# uArm_back_print.net
KiCad netlist of a schematic drawn in EAGLE
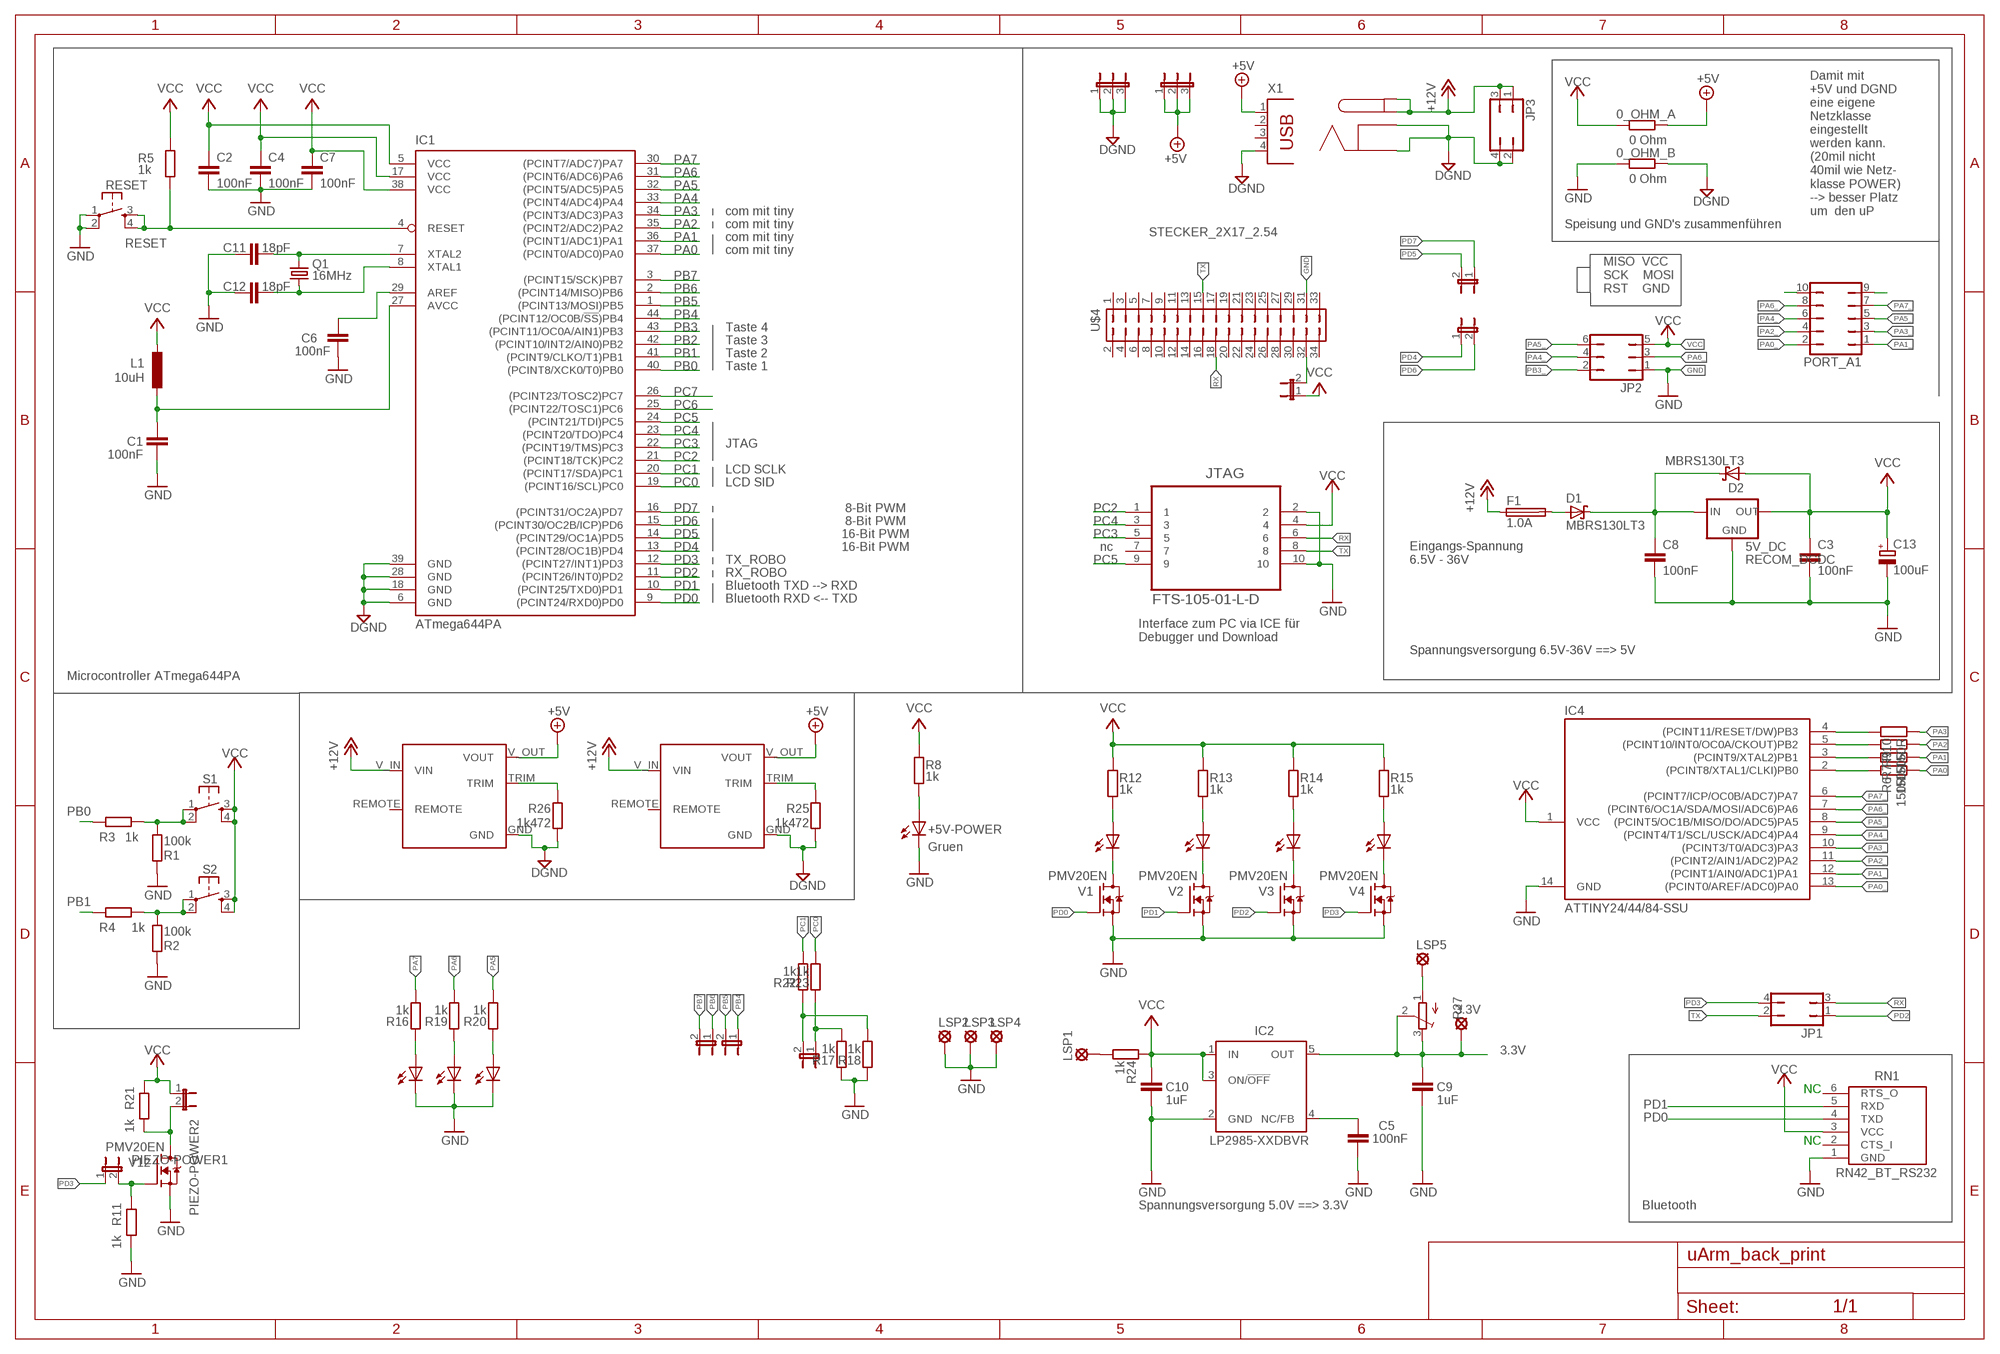
[diagram p0: schematic, sheet 1]

(export (version "E")
  (design (tool "Eeschema 10.0.6"))
  (components
    (comp (ref "+5V-POWER")
      (value "Gruen")
      (footprint "eagle-import:CHIPLED_1206")
      (libsource (lib "eagle-import") (part "LEDCHIPLED_1206"))
    )
    (comp (ref "0_OHM_A")
      (value "0 Ohm")
      (footprint "eagle-import:R0805")
      (libsource (lib "eagle-import") (part "R-EU_R0805"))
    )
    (comp (ref "0_OHM_B")
      (value "0 Ohm")
      (footprint "eagle-import:R0805")
      (libsource (lib "eagle-import") (part "R-EU_R0805"))
    )
    (comp (ref "3.3V")
      (value "3.3V")
      (footprint "eagle-import:LSP11")
      (libsource (lib "eagle-import") (part "LSP11"))
    )
    (comp (ref "5V_DC")
      (value "RECOM_DCDC")
      (footprint "eagle-import:RECOM_DCDC")
      (libsource (lib "eagle-import") (part "RECOM_DCDC"))
    )
    (comp (ref "C1")
      (value "100nF")
      (footprint "eagle-import:C0805")
      (libsource (lib "eagle-import") (part "C-EUC0805"))
    )
    (comp (ref "C2")
      (value "100nF")
      (footprint "eagle-import:C0805")
      (libsource (lib "eagle-import") (part "C-EUC0805"))
    )
    (comp (ref "C3")
      (value "100nF")
      (footprint "eagle-import:C0805")
      (libsource (lib "eagle-import") (part "C-EUC0805"))
    )
    (comp (ref "C4")
      (value "100nF")
      (footprint "eagle-import:C0805")
      (libsource (lib "eagle-import") (part "C-EUC0805"))
    )
    (comp (ref "C5")
      (value "100nF")
      (footprint "eagle-import:C0805")
      (libsource (lib "eagle-import") (part "C-EUC0805"))
    )
    (comp (ref "C6")
      (value "100nF")
      (footprint "eagle-import:C0805")
      (libsource (lib "eagle-import") (part "C-EUC0805"))
    )
    (comp (ref "C7")
      (value "100nF")
      (footprint "eagle-import:C0805")
      (libsource (lib "eagle-import") (part "C-EUC0805"))
    )
    (comp (ref "C8")
      (value "100nF")
      (footprint "eagle-import:C0805")
      (libsource (lib "eagle-import") (part "C-EUC0805"))
    )
    (comp (ref "C9")
      (value "1uF")
      (footprint "eagle-import:C0805")
      (libsource (lib "eagle-import") (part "C-EUC0805"))
    )
    (comp (ref "C10")
      (value "1uF")
      (footprint "eagle-import:C0805")
      (libsource (lib "eagle-import") (part "C-EUC0805"))
    )
    (comp (ref "C11")
      (value "18pF")
      (footprint "eagle-import:C0805")
      (libsource (lib "eagle-import") (part "C-EUC0805"))
    )
    (comp (ref "C12")
      (value "18pF")
      (footprint "eagle-import:C0805")
      (libsource (lib "eagle-import") (part "C-EUC0805"))
    )
    (comp (ref "C13")
      (value "100uF")
      (footprint "eagle-import:UD-6,3X5,8_NICHICON")
      (libsource (lib "eagle-import") (part "CPOL-EUUD-6,3X8,8"))
    )
    (comp (ref "D1")
      (value "MBRS130LT3")
      (footprint "eagle-import:SMB")
      (libsource (lib "eagle-import") (part "MBRS130LT3"))
    )
    (comp (ref "D2")
      (value "MBRS130LT3")
      (footprint "eagle-import:SMB")
      (libsource (lib "eagle-import") (part "MBRS130LT3"))
    )
    (comp (ref "F1")
      (value "1.0A")
      (footprint "eagle-import:F1206")
      (libsource (lib "eagle-import") (part "195601206"))
    )
    (comp (ref "IC1")
      (value "ATmega644PA")
      (footprint "eagle-import:TQFP44")
      (fields (field (name "MPN") "ATMEGA644PV-10AU"))
      (libsource (lib "eagle-import") (part "ATMEGA644A"))
    )
    (comp (ref "IC2")
      (value "LP2985-XXDBVR")
      (footprint "eagle-import:SOT23-DBV")
      (libsource (lib "eagle-import") (part "LP2985-XXDBVR"))
    )
    (comp (ref "IC4")
      (value "ATTINY24/44/84-SSU")
      (footprint "eagle-import:SOIC14")
      (libsource (lib "eagle-import") (part "ATTINY24/44/84-SSU"))
    )
    (comp (ref "JP1")
      (value "JP2Q")
      (footprint "eagle-import:JP2Q")
      (libsource (lib "eagle-import") (part "JP2Q"))
    )
    (comp (ref "JP2")
      (value "JP3Q")
      (footprint "eagle-import:JP3Q")
      (libsource (lib "eagle-import") (part "JP3Q"))
    )
    (comp (ref "JP3")
      (value "JP2Q")
      (footprint "eagle-import:JP2Q")
      (libsource (lib "eagle-import") (part "JP2Q"))
    )
    (comp (ref "JTAG")
      (value "FTS-105-01-L-D")
      (footprint "eagle-import:SAMTEC_FTS-105-01-L-D")
      (libsource (lib "eagle-import") (part "FTS-105-01-L-D"))
    )
    (comp (ref "L1")
      (value "10uH")
      (footprint "eagle-import:L2825P")
      (libsource (lib "eagle-import") (part "L-EUL2825P"))
    )
    (comp (ref "LSP1")
      (value "LSP11")
      (footprint "eagle-import:LSP11")
      (libsource (lib "eagle-import") (part "solpad_364_LSP11"))
    )
    (comp (ref "LSP2")
      (value "LSP11")
      (footprint "eagle-import:LSP11")
      (libsource (lib "eagle-import") (part "solpad_364_LSP11"))
    )
    (comp (ref "LSP3")
      (value "LSP11")
      (footprint "eagle-import:LSP11")
      (libsource (lib "eagle-import") (part "solpad_364_LSP11"))
    )
    (comp (ref "LSP4")
      (value "LSP11")
      (footprint "eagle-import:LSP11")
      (libsource (lib "eagle-import") (part "solpad_364_LSP11"))
    )
    (comp (ref "LSP5")
      (value "LSP11")
      (footprint "eagle-import:LSP11")
      (libsource (lib "eagle-import") (part "solpad_364_LSP11"))
    )
    (comp (ref "PIEZO-POWER1")
      (value "JP1E")
      (footprint "eagle-import:JP1")
      (libsource (lib "eagle-import") (part "JP1E"))
    )
    (comp (ref "PIEZO-POWER2")
      (value "JP1E")
      (footprint "eagle-import:JP1")
      (libsource (lib "eagle-import") (part "JP1E"))
    )
    (comp (ref "PIEZO-POWER3")
      (value "JP1E")
      (footprint "eagle-import:JP1")
      (libsource (lib "eagle-import") (part "JP1E"))
    )
    (comp (ref "PIEZO-POWER4")
      (value "JP1E")
      (footprint "eagle-import:JP1")
      (libsource (lib "eagle-import") (part "JP1E"))
    )
    (comp (ref "PIEZO-POWER5")
      (value "JP1E")
      (footprint "eagle-import:JP1")
      (libsource (lib "eagle-import") (part "JP1E"))
    )
    (comp (ref "PIEZO-POWER8")
      (value "JP1E")
      (footprint "eagle-import:JP1")
      (libsource (lib "eagle-import") (part "JP1E"))
    )
    (comp (ref "PIEZO-POWER9")
      (value "JP1E")
      (footprint "eagle-import:JP1")
      (libsource (lib "eagle-import") (part "JP1E"))
    )
    (comp (ref "PIEZO-POWER10")
      (value "JP1E")
      (footprint "eagle-import:JP1")
      (libsource (lib "eagle-import") (part "JP1E"))
    )
    (comp (ref "PORT_A1")
      (value "JP5Q")
      (footprint "eagle-import:JP5Q")
      (libsource (lib "eagle-import") (part "JP5Q"))
    )
    (comp (ref "Q1")
      (value "16MHz")
      (footprint "eagle-import:HC49UP")
      (libsource (lib "eagle-import") (part "CRYSTALHC49UP"))
    )
    (comp (ref "R1")
      (value "100k")
      (footprint "eagle-import:R0805")
      (libsource (lib "eagle-import") (part "R-EU_R0805"))
    )
    (comp (ref "R2")
      (value "100k")
      (footprint "eagle-import:R0805")
      (libsource (lib "eagle-import") (part "R-EU_R0805"))
    )
    (comp (ref "R3")
      (value "1k")
      (footprint "eagle-import:R0805")
      (libsource (lib "eagle-import") (part "R-EU_R0805"))
    )
    (comp (ref "R4")
      (value "1k")
      (footprint "eagle-import:R0805")
      (libsource (lib "eagle-import") (part "R-EU_R0805"))
    )
    (comp (ref "R5")
      (value "1k")
      (footprint "eagle-import:R0805")
      (libsource (lib "eagle-import") (part "R-EU_R0805"))
    )
    (comp (ref "R6")
      (value "150R")
      (footprint "eagle-import:R0805")
      (libsource (lib "eagle-import") (part "R-EU_R0805"))
    )
    (comp (ref "R7")
      (value "150R")
      (footprint "eagle-import:R0805")
      (libsource (lib "eagle-import") (part "R-EU_R0805"))
    )
    (comp (ref "R8")
      (value "1k")
      (footprint "eagle-import:R0805")
      (libsource (lib "eagle-import") (part "R-EU_R0805"))
    )
    (comp (ref "R9")
      (value "150R")
      (footprint "eagle-import:R0805")
      (libsource (lib "eagle-import") (part "R-EU_R0805"))
    )
    (comp (ref "R10")
      (value "150R")
      (footprint "eagle-import:R0805")
      (libsource (lib "eagle-import") (part "R-EU_R0805"))
    )
    (comp (ref "R11")
      (value "1k")
      (footprint "eagle-import:R0805")
      (libsource (lib "eagle-import") (part "R-EU_R0805"))
    )
    (comp (ref "R12")
      (value "1k")
      (footprint "eagle-import:R0805")
      (libsource (lib "eagle-import") (part "R-EU_R0805"))
    )
    (comp (ref "R13")
      (value "1k")
      (footprint "eagle-import:R0805")
      (libsource (lib "eagle-import") (part "R-EU_R0805"))
    )
    (comp (ref "R14")
      (value "1k")
      (footprint "eagle-import:R0805")
      (libsource (lib "eagle-import") (part "R-EU_R0805"))
    )
    (comp (ref "R15")
      (value "1k")
      (footprint "eagle-import:R0805")
      (libsource (lib "eagle-import") (part "R-EU_R0805"))
    )
    (comp (ref "R16")
      (value "1k")
      (footprint "eagle-import:R0805")
      (libsource (lib "eagle-import") (part "R-EU_R0805"))
    )
    (comp (ref "R17")
      (value "1k")
      (footprint "eagle-import:R0805")
      (libsource (lib "eagle-import") (part "R-EU_R0805"))
    )
    (comp (ref "R18")
      (value "1k")
      (footprint "eagle-import:R0805")
      (libsource (lib "eagle-import") (part "R-EU_R0805"))
    )
    (comp (ref "R19")
      (value "1k")
      (footprint "eagle-import:R0805")
      (libsource (lib "eagle-import") (part "R-EU_R0805"))
    )
    (comp (ref "R20")
      (value "1k")
      (footprint "eagle-import:R0805")
      (libsource (lib "eagle-import") (part "R-EU_R0805"))
    )
    (comp (ref "R21")
      (value "1k")
      (footprint "eagle-import:R0805")
      (libsource (lib "eagle-import") (part "R-EU_R0805"))
    )
    (comp (ref "R22")
      (value "1k")
      (footprint "eagle-import:R0805")
      (libsource (lib "eagle-import") (part "R-EU_R0805"))
    )
    (comp (ref "R23")
      (value "1k")
      (footprint "eagle-import:R0805")
      (libsource (lib "eagle-import") (part "R-EU_R0805"))
    )
    (comp (ref "R24")
      (value "1k")
      (footprint "eagle-import:R0805")
      (libsource (lib "eagle-import") (part "R-EU_R0805"))
    )
    (comp (ref "R25")
      (value "1k472")
      (footprint "eagle-import:R0805")
      (libsource (lib "eagle-import") (part "R-EU_R0805"))
    )
    (comp (ref "R26")
      (value "1k472")
      (footprint "eagle-import:R0805")
      (libsource (lib "eagle-import") (part "R-EU_R0805"))
    )
    (comp (ref "R27")
      (value "TRIM_EU-3223G")
      (footprint "eagle-import:3223G")
      (libsource (lib "eagle-import") (part "TRIM_EU-3223G"))
    )
    (comp (ref "RESET")
      (value "TS42_4PAD")
      (footprint "eagle-import:TS42_4PAD")
      (libsource (lib "eagle-import") (part "TS42_4PAD"))
    )
    (comp (ref "RN1")
      (value "RN42_BT_RS232")
      (footprint "eagle-import:RN42BT_RS232")
      (libsource (lib "eagle-import") (part "RN42_BT_RS232"))
    )
    (comp (ref "RX1")
      (value "Gruen")
      (footprint "eagle-import:CHIPLED_1206")
      (libsource (lib "eagle-import") (part "LEDCHIPLED_1206"))
    )
    (comp (ref "RX2")
      (value "Gruen")
      (footprint "eagle-import:CHIPLED_1206")
      (libsource (lib "eagle-import") (part "LEDCHIPLED_1206"))
    )
    (comp (ref "S1")
      (value "TS42_4PAD")
      (footprint "eagle-import:TS42_4PAD")
      (libsource (lib "eagle-import") (part "TS42_4PAD"))
    )
    (comp (ref "S2")
      (value "TS42_4PAD")
      (footprint "eagle-import:TS42_4PAD")
      (libsource (lib "eagle-import") (part "TS42_4PAD"))
    )
    (comp (ref "TX1")
      (value "Gruen")
      (footprint "eagle-import:CHIPLED_1206")
      (libsource (lib "eagle-import") (part "LEDCHIPLED_1206"))
    )
    (comp (ref "TX2")
      (value "Gruen")
      (footprint "eagle-import:CHIPLED_1206")
      (libsource (lib "eagle-import") (part "LEDCHIPLED_1206"))
    )
    (comp (ref "TX3")
      (value "Gruen")
      (footprint "eagle-import:CHIPLED_1206")
      (libsource (lib "eagle-import") (part "LEDCHIPLED_1206"))
    )
    (comp (ref "TX4")
      (value "Gruen")
      (footprint "eagle-import:CHIPLED_1206")
      (libsource (lib "eagle-import") (part "LEDCHIPLED_1206"))
    )
    (comp (ref "TX5")
      (value "Gruen")
      (footprint "eagle-import:CHIPLED_1206")
      (libsource (lib "eagle-import") (part "LEDCHIPLED_1206"))
    )
    (comp (ref "U$1")
      (value "BUCHSE")
      (footprint "eagle-import:BUCHSE")
      (libsource (lib "eagle-import") (part "BUCHSE"))
    )
    (comp (ref "U$2")
      (value "DCDC")
      (footprint "eagle-import:1X2,3_2.54MM")
      (libsource (lib "eagle-import") (part "DCDC"))
    )
    (comp (ref "U$3")
      (value "DCDC")
      (footprint "eagle-import:1X2,3_2.54MM")
      (libsource (lib "eagle-import") (part "DCDC"))
    )
    (comp (ref "U$4")
      (value "STECKER_2X17_2.54")
      (footprint "eagle-import:2X17_2.54")
      (libsource (lib "eagle-import") (part "STECKER_2X17_2.54"))
    )
    (comp (ref "UART_ROBO1")
      (value "JP2E")
      (footprint "eagle-import:JP2")
      (libsource (lib "eagle-import") (part "JP2E"))
    )
    (comp (ref "UART_ROBO2")
      (value "JP2E")
      (footprint "eagle-import:JP2")
      (libsource (lib "eagle-import") (part "JP2E"))
    )
    (comp (ref "V1")
      (value "PMV20EN")
      (footprint "eagle-import:SOT23")
      (libsource (lib "eagle-import") (part "BSS138"))
    )
    (comp (ref "V2")
      (value "PMV20EN")
      (footprint "eagle-import:SOT23")
      (libsource (lib "eagle-import") (part "BSS138"))
    )
    (comp (ref "V3")
      (value "PMV20EN")
      (footprint "eagle-import:SOT23")
      (libsource (lib "eagle-import") (part "BSS138"))
    )
    (comp (ref "V4")
      (value "PMV20EN")
      (footprint "eagle-import:SOT23")
      (libsource (lib "eagle-import") (part "BSS138"))
    )
    (comp (ref "V12")
      (value "PMV20EN")
      (footprint "eagle-import:SOT23")
      (libsource (lib "eagle-import") (part "BSS138"))
    )
    (comp (ref "X1")
      (value "PN87520")
      (footprint "eagle-import:PN87520")
      (libsource (lib "eagle-import") (part "PN87520"))
    )
  )
  (nets
    (net (code "1") (name "+5V") (class "Default")
      (node (ref "0_OHM_A") (pin "2") (pinfunction "2_2") (pintype "passive"))
      (node (ref "U$2") (pin "V_OUT") (pinfunction "VOUT_V_OUT") (pintype "bidirectional"))
      (node (ref "U$3") (pin "V_OUT") (pinfunction "VOUT_V_OUT") (pintype "bidirectional"))
      (node (ref "UART_ROBO1") (pin "1") (pinfunction "1_1") (pintype "passive"))
      (node (ref "UART_ROBO1") (pin "2") (pinfunction "2_2") (pintype "passive"))
      (node (ref "UART_ROBO1") (pin "3") (pinfunction "3_3") (pintype "passive"))
      (node (ref "X1") (pin "1") (pinfunction "1_1") (pintype "passive"))
    )
    (net (code "2") (name "+12V") (class "Default")
      (node (ref "F1") (pin "1") (pinfunction "1_1") (pintype "passive"))
      (node (ref "JP3") (pin "1") (pinfunction "1_1") (pintype "passive"))
      (node (ref "JP3") (pin "3") (pinfunction "3_3") (pintype "passive"))
      (node (ref "U$1") (pin "3") (pinfunction "3_3") (pintype "bidirectional"))
      (node (ref "U$1") (pin "3.1") (pinfunction "3.1_3.1") (pintype "bidirectional"))
      (node (ref "U$2") (pin "V_IN") (pinfunction "VIN_V_IN") (pintype "bidirectional"))
      (node (ref "U$3") (pin "V_IN") (pinfunction "VIN_V_IN") (pintype "bidirectional"))
    )
    (net (code "3") (name "/3.3V") (class "Default")
      (node (ref "3.3V") (pin "MP") (pinfunction "MP_MP") (pintype "passive"))
      (node (ref "C9") (pin "1") (pinfunction "1_1") (pintype "passive"))
      (node (ref "IC2") (pin "5") (pinfunction "OUT_5") (pintype "passive"))
      (node (ref "R27") (pin "2") (pinfunction "S_2") (pintype "passive"))
      (node (ref "R27") (pin "3") (pinfunction "E_3") (pintype "passive"))
    )
    (net (code "4") (name "/PA4") (class "Default")
      (node (ref "IC1") (pin "33") (pinfunction "(PCINT4/ADC4)PA4_33") (pintype "bidirectional"))
    )
    (net (code "5") (name "/PB0") (class "Default")
      (node (ref "IC1") (pin "40") (pinfunction "(PCINT8/XCK0/T0)PB0_40") (pintype "bidirectional"))
      (node (ref "R3") (pin "1") (pinfunction "1_1") (pintype "passive"))
    )
    (net (code "6") (name "/PB1") (class "Default")
      (node (ref "IC1") (pin "41") (pinfunction "(PCINT9/CLKO/T1)PB1_41") (pintype "bidirectional"))
      (node (ref "R4") (pin "1") (pinfunction "1_1") (pintype "passive"))
    )
    (net (code "7") (name "/PB2") (class "Default")
      (node (ref "IC1") (pin "42") (pinfunction "(PCINT10/INT2/AIN0)PB2_42") (pintype "bidirectional"))
    )
    (net (code "8") (name "/PB3") (class "Default")
      (node (ref "IC1") (pin "43") (pinfunction "(PCINT11/OC0A/AIN1)PB3_43") (pintype "bidirectional"))
    )
    (net (code "9") (name "/PC2") (class "Default")
      (node (ref "IC1") (pin "21") (pinfunction "(PCINT18/TCK)PC2_21") (pintype "output"))
      (node (ref "JTAG") (pin "1") (pinfunction "1_1") (pintype "passive"))
    )
    (net (code "10") (name "/PC3") (class "Default")
      (node (ref "IC1") (pin "22") (pinfunction "(PCINT19/TMS)PC3_22") (pintype "output"))
      (node (ref "JTAG") (pin "5") (pinfunction "5_5") (pintype "passive"))
    )
    (net (code "11") (name "/PC4") (class "Default")
      (node (ref "IC1") (pin "23") (pinfunction "(PCINT20/TDO)PC4_23") (pintype "output"))
      (node (ref "JTAG") (pin "3") (pinfunction "3_3") (pintype "passive"))
    )
    (net (code "12") (name "/PC5") (class "Default")
      (node (ref "IC1") (pin "24") (pinfunction "(PCINT21/TDI)PC5_24") (pintype "output"))
      (node (ref "JTAG") (pin "9") (pinfunction "9_9") (pintype "passive"))
    )
    (net (code "13") (name "/PC6") (class "Default")
      (node (ref "IC1") (pin "25") (pinfunction "(PCINT22/TOSC1)PC6_25") (pintype "output"))
    )
    (net (code "14") (name "/PC7") (class "Default")
      (node (ref "IC1") (pin "26") (pinfunction "(PCINT23/TOSC2)PC7_26") (pintype "output"))
    )
    (net (code "15") (name "/RESET") (class "Default")
      (node (ref "IC1") (pin "4") (pinfunction "RESET_4") (pintype "input"))
      (node (ref "R5") (pin "1") (pinfunction "1_1") (pintype "passive"))
      (node (ref "RESET") (pin "3") (pinfunction "3_3") (pintype "passive"))
      (node (ref "RESET") (pin "4") (pinfunction "4_4") (pintype "passive"))
    )
    (net (code "16") (name "DGND") (class "Default")
      (node (ref "0_OHM_B") (pin "2") (pinfunction "2_2") (pintype "passive"))
      (node (ref "IC1") (pin "18") (pinfunction "GND_18") (pintype "power_in"))
      (node (ref "IC1") (pin "28") (pinfunction "GND_28") (pintype "power_in"))
      (node (ref "IC1") (pin "39") (pinfunction "GND_39") (pintype "power_in"))
      (node (ref "IC1") (pin "6") (pinfunction "GND_6") (pintype "power_in"))
      (node (ref "JP3") (pin "2") (pinfunction "2_2") (pintype "passive"))
      (node (ref "JP3") (pin "4") (pinfunction "4_4") (pintype "passive"))
      (node (ref "R25") (pin "1") (pinfunction "1_1") (pintype "passive"))
      (node (ref "R26") (pin "1") (pinfunction "1_1") (pintype "passive"))
      (node (ref "U$1") (pin "1") (pinfunction "1_1") (pintype "bidirectional"))
      (node (ref "U$1") (pin "2") (pinfunction "2_2") (pintype "bidirectional"))
      (node (ref "U$2") (pin "GND") (pinfunction "GND_GND") (pintype "bidirectional"))
      (node (ref "U$3") (pin "GND") (pinfunction "GND_GND") (pintype "bidirectional"))
      (node (ref "UART_ROBO2") (pin "1") (pinfunction "1_1") (pintype "passive"))
      (node (ref "UART_ROBO2") (pin "2") (pinfunction "2_2") (pintype "passive"))
      (node (ref "UART_ROBO2") (pin "3") (pinfunction "3_3") (pintype "passive"))
      (node (ref "X1") (pin "4") (pinfunction "4_4") (pintype "passive"))
    )
    (net (code "17") (name "GND") (class "Default")
      (node (ref "+5V-POWER") (pin "C") (pinfunction "C_C") (pintype "passive"))
      (node (ref "0_OHM_B") (pin "1") (pinfunction "1_1") (pintype "passive"))
      (node (ref "5V_DC") (pin "GND") (pinfunction "GND_GND") (pintype "input"))
      (node (ref "C1") (pin "1") (pinfunction "1_1") (pintype "passive"))
      (node (ref "C10") (pin "2") (pinfunction "2_2") (pintype "passive"))
      (node (ref "C11") (pin "1") (pinfunction "1_1") (pintype "passive"))
      (node (ref "C12") (pin "2") (pinfunction "2_2") (pintype "passive"))
      (node (ref "C13") (pin "-") (pinfunction "-_-") (pintype "passive"))
      (node (ref "C2") (pin "2") (pinfunction "2_2") (pintype "passive"))
      (node (ref "C3") (pin "2") (pinfunction "2_2") (pintype "passive"))
      (node (ref "C4") (pin "2") (pinfunction "2_2") (pintype "passive"))
      (node (ref "C5") (pin "2") (pinfunction "2_2") (pintype "passive"))
      (node (ref "C6") (pin "1") (pinfunction "1_1") (pintype "passive"))
      (node (ref "C7") (pin "2") (pinfunction "2_2") (pintype "passive"))
      (node (ref "C8") (pin "2") (pinfunction "2_2") (pintype "passive"))
      (node (ref "C9") (pin "2") (pinfunction "2_2") (pintype "passive"))
      (node (ref "IC2") (pin "2") (pinfunction "GND_2") (pintype "power_in"))
      (node (ref "IC4") (pin "14") (pinfunction "GND_14") (pintype "power_in"))
      (node (ref "JP2") (pin "1") (pinfunction "1_1") (pintype "passive"))
      (node (ref "JTAG") (pin "10") (pinfunction "10_10") (pintype "passive"))
      (node (ref "JTAG") (pin "2") (pinfunction "2_2") (pintype "passive"))
      (node (ref "LSP2") (pin "MP") (pinfunction "MP_MP") (pintype "passive"))
      (node (ref "LSP3") (pin "MP") (pinfunction "MP_MP") (pintype "passive"))
      (node (ref "LSP4") (pin "MP") (pinfunction "MP_MP") (pintype "passive"))
      (node (ref "R1") (pin "1") (pinfunction "1_1") (pintype "passive"))
      (node (ref "R11") (pin "2") (pinfunction "2_2") (pintype "passive"))
      (node (ref "R17") (pin "2") (pinfunction "2_2") (pintype "passive"))
      (node (ref "R18") (pin "2") (pinfunction "2_2") (pintype "passive"))
      (node (ref "R2") (pin "1") (pinfunction "1_1") (pintype "passive"))
      (node (ref "RESET") (pin "1") (pinfunction "1_1") (pintype "passive"))
      (node (ref "RESET") (pin "2") (pinfunction "2_2") (pintype "passive"))
      (node (ref "RN1") (pin "1") (pinfunction "GND_1") (pintype "bidirectional"))
      (node (ref "TX3") (pin "C") (pinfunction "C_C") (pintype "passive"))
      (node (ref "TX4") (pin "C") (pinfunction "C_C") (pintype "passive"))
      (node (ref "TX5") (pin "C") (pinfunction "C_C") (pintype "passive"))
      (node (ref "U$4") (pin "31") (pinfunction "31_31") (pintype "passive"))
      (node (ref "V1") (pin "2") (pinfunction "S_2") (pintype "passive"))
      (node (ref "V12") (pin "2") (pinfunction "S_2") (pintype "passive"))
      (node (ref "V2") (pin "2") (pinfunction "S_2") (pintype "passive"))
      (node (ref "V3") (pin "2") (pinfunction "S_2") (pintype "passive"))
      (node (ref "V4") (pin "2") (pinfunction "S_2") (pintype "passive"))
    )
    (net (code "18") (name "Net-(+5V-POWER-PadA)") (class "Default")
      (node (ref "+5V-POWER") (pin "A") (pinfunction "A_A") (pintype "passive"))
      (node (ref "R8") (pin "1") (pinfunction "1_1") (pintype "passive"))
    )
    (net (code "19") (name "Net-(5V_DC-PadIN)") (class "Default")
      (node (ref "5V_DC") (pin "IN") (pinfunction "IN_IN") (pintype "input"))
      (node (ref "C8") (pin "1") (pinfunction "1_1") (pintype "passive"))
      (node (ref "D1") (pin "C") (pinfunction "C_C") (pintype "passive"))
      (node (ref "D2") (pin "C") (pinfunction "C_C") (pintype "passive"))
    )
    (net (code "20") (name "Net-(D1-PadA)") (class "Default")
      (node (ref "D1") (pin "A") (pinfunction "A_A") (pintype "passive"))
      (node (ref "F1") (pin "2") (pinfunction "2_2") (pintype "passive"))
    )
    (net (code "21") (name "Net-(IC1-AREF)") (class "Default")
      (node (ref "C6") (pin "2") (pinfunction "2_2") (pintype "passive"))
      (node (ref "IC1") (pin "29") (pinfunction "AREF_29") (pintype "passive"))
    )
    (net (code "22") (name "Net-(IC1-AVCC)") (class "Default")
      (node (ref "C1") (pin "2") (pinfunction "2_2") (pintype "passive"))
      (node (ref "IC1") (pin "27") (pinfunction "AVCC_27") (pintype "passive"))
      (node (ref "L1") (pin "2") (pinfunction "2_2") (pintype "passive"))
    )
    (net (code "23") (name "Net-(IC1-XTAL1)") (class "Default")
      (node (ref "C12") (pin "1") (pinfunction "1_1") (pintype "passive"))
      (node (ref "IC1") (pin "8") (pinfunction "XTAL1_8") (pintype "bidirectional"))
      (node (ref "Q1") (pin "1") (pinfunction "1_1") (pintype "passive"))
    )
    (net (code "24") (name "Net-(IC1-XTAL2)") (class "Default")
      (node (ref "C11") (pin "2") (pinfunction "2_2") (pintype "passive"))
      (node (ref "IC1") (pin "7") (pinfunction "XTAL2_7") (pintype "bidirectional"))
      (node (ref "Q1") (pin "2") (pinfunction "2_2") (pintype "passive"))
    )
    (net (code "25") (name "Net-(IC2-NC{slash}FB)") (class "Default")
      (node (ref "C5") (pin "1") (pinfunction "1_1") (pintype "passive"))
      (node (ref "IC2") (pin "4") (pinfunction "NC/FB_4") (pintype "passive"))
    )
    (net (code "26") (name "Net-(IC4-(PCINT8{slash}XTAL1{slash}CLKI)PB0)") (class "Default")
      (node (ref "IC4") (pin "2") (pinfunction "(PCINT8/XTAL1/CLKI)PB0_2") (pintype "bidirectional"))
      (node (ref "R6") (pin "2") (pinfunction "2_2") (pintype "passive"))
    )
    (net (code "27") (name "Net-(IC4-(PCINT9{slash}XTAL2)PB1)") (class "Default")
      (node (ref "IC4") (pin "3") (pinfunction "(PCINT9/XTAL2)PB1_3") (pintype "bidirectional"))
      (node (ref "R7") (pin "2") (pinfunction "2_2") (pintype "passive"))
    )
    (net (code "28") (name "Net-(IC4-(PCINT10{slash}INT0{slash}OC0A{slash}CKOUT)PB2)") (class "Default")
      (node (ref "IC4") (pin "5") (pinfunction "(PCINT10/INT0/OC0A/CKOUT)PB2_5") (pintype "bidirectional"))
      (node (ref "R9") (pin "2") (pinfunction "2_2") (pintype "passive"))
    )
    (net (code "29") (name "Net-(LSP1-PadMP)") (class "Default")
      (node (ref "LSP1") (pin "MP") (pinfunction "MP_MP") (pintype "passive"))
      (node (ref "R24") (pin "1") (pinfunction "1_1") (pintype "passive"))
    )
    (net (code "30") (name "Net-(PIEZO-POWER4-Pad2)") (class "Default")
      (node (ref "PIEZO-POWER4") (pin "2") (pinfunction "2_2") (pintype "passive"))
      (node (ref "U$4") (pin "32") (pinfunction "32_32") (pintype "passive"))
    )
    (net (code "31") (name "Net-(PIEZO-POWER10-Pad1)") (class "Default")
      (node (ref "PIEZO-POWER10") (pin "1") (pinfunction "1_1") (pintype "passive"))
      (node (ref "R17") (pin "1") (pinfunction "1_1") (pintype "passive"))
      (node (ref "R23") (pin "2") (pinfunction "2_2") (pintype "passive"))
    )
    (net (code "32") (name "Net-(PIEZO-POWER10-Pad2)") (class "Default")
      (node (ref "PIEZO-POWER10") (pin "2") (pinfunction "2_2") (pintype "passive"))
      (node (ref "R18") (pin "1") (pinfunction "1_1") (pintype "passive"))
      (node (ref "R22") (pin "2") (pinfunction "2_2") (pintype "passive"))
    )
    (net (code "33") (name "Net-(R1-Pad2)") (class "Default")
      (node (ref "R1") (pin "2") (pinfunction "2_2") (pintype "passive"))
      (node (ref "R3") (pin "2") (pinfunction "2_2") (pintype "passive"))
      (node (ref "S1") (pin "1") (pinfunction "1_1") (pintype "passive"))
      (node (ref "S1") (pin "2") (pinfunction "2_2") (pintype "passive"))
    )
    (net (code "34") (name "Net-(R2-Pad2)") (class "Default")
      (node (ref "R2") (pin "2") (pinfunction "2_2") (pintype "passive"))
      (node (ref "R4") (pin "2") (pinfunction "2_2") (pintype "passive"))
      (node (ref "S2") (pin "1") (pinfunction "1_1") (pintype "passive"))
      (node (ref "S2") (pin "2") (pinfunction "2_2") (pintype "passive"))
    )
    (net (code "35") (name "Net-(R12-Pad1)") (class "Default")
      (node (ref "R12") (pin "1") (pinfunction "1_1") (pintype "passive"))
      (node (ref "RX1") (pin "A") (pinfunction "A_A") (pintype "passive"))
    )
    (net (code "36") (name "Net-(R13-Pad1)") (class "Default")
      (node (ref "R13") (pin "1") (pinfunction "1_1") (pintype "passive"))
      (node (ref "TX1") (pin "A") (pinfunction "A_A") (pintype "passive"))
    )
    (net (code "37") (name "Net-(R14-Pad1)") (class "Default")
      (node (ref "R14") (pin "1") (pinfunction "1_1") (pintype "passive"))
      (node (ref "TX2") (pin "A") (pinfunction "A_A") (pintype "passive"))
    )
    (net (code "38") (name "Net-(R15-Pad1)") (class "Default")
      (node (ref "R15") (pin "1") (pinfunction "1_1") (pintype "passive"))
      (node (ref "RX2") (pin "A") (pinfunction "A_A") (pintype "passive"))
    )
    (net (code "39") (name "Net-(R16-Pad2)") (class "Default")
      (node (ref "R16") (pin "2") (pinfunction "2_2") (pintype "passive"))
      (node (ref "TX5") (pin "A") (pinfunction "A_A") (pintype "passive"))
    )
    (net (code "40") (name "Net-(R19-Pad2)") (class "Default")
      (node (ref "R19") (pin "2") (pinfunction "2_2") (pintype "passive"))
      (node (ref "TX4") (pin "A") (pinfunction "A_A") (pintype "passive"))
    )
    (net (code "41") (name "Net-(R20-Pad2)") (class "Default")
      (node (ref "R20") (pin "2") (pinfunction "2_2") (pintype "passive"))
      (node (ref "TX3") (pin "A") (pinfunction "A_A") (pintype "passive"))
    )
    (net (code "42") (name "Net-(R25-Pad2)") (class "Default")
      (node (ref "R25") (pin "2") (pinfunction "2_2") (pintype "passive"))
      (node (ref "U$2") (pin "TRIM") (pinfunction "TRIM_TRIM") (pintype "bidirectional"))
    )
    (net (code "43") (name "Net-(R26-Pad2)") (class "Default")
      (node (ref "R26") (pin "2") (pinfunction "2_2") (pintype "passive"))
      (node (ref "U$3") (pin "TRIM") (pinfunction "TRIM_TRIM") (pintype "bidirectional"))
    )
    (net (code "44") (name "Net-(R27-A)") (class "Default")
      (node (ref "LSP5") (pin "MP") (pinfunction "MP_MP") (pintype "passive"))
      (node (ref "R27") (pin "1") (pinfunction "A_1") (pintype "passive"))
    )
    (net (code "45") (name "Net-(V1-D)") (class "Default")
      (node (ref "RX1") (pin "C") (pinfunction "C_C") (pintype "passive"))
      (node (ref "V1") (pin "3") (pinfunction "D_3") (pintype "passive"))
    )
    (net (code "46") (name "Net-(V2-D)") (class "Default")
      (node (ref "TX1") (pin "C") (pinfunction "C_C") (pintype "passive"))
      (node (ref "V2") (pin "3") (pinfunction "D_3") (pintype "passive"))
    )
    (net (code "47") (name "Net-(V3-D)") (class "Default")
      (node (ref "TX2") (pin "C") (pinfunction "C_C") (pintype "passive"))
      (node (ref "V3") (pin "3") (pinfunction "D_3") (pintype "passive"))
    )
    (net (code "48") (name "Net-(V4-D)") (class "Default")
      (node (ref "RX2") (pin "C") (pinfunction "C_C") (pintype "passive"))
      (node (ref "V4") (pin "3") (pinfunction "D_3") (pintype "passive"))
    )
    (net (code "49") (name "Net-(V12-D)") (class "Default")
      (node (ref "PIEZO-POWER2") (pin "2") (pinfunction "2_2") (pintype "passive"))
      (node (ref "R21") (pin "2") (pinfunction "2_2") (pintype "passive"))
      (node (ref "V12") (pin "3") (pinfunction "D_3") (pintype "passive"))
    )
    (net (code "50") (name "Net-(V12-G)") (class "Default")
      (node (ref "PIEZO-POWER1") (pin "2") (pinfunction "2_2") (pintype "passive"))
      (node (ref "R11") (pin "1") (pinfunction "1_1") (pintype "passive"))
      (node (ref "V12") (pin "1") (pinfunction "G_1") (pintype "passive"))
    )
    (net (code "51") (name "PA0") (class "Default")
      (node (ref "IC1") (pin "37") (pinfunction "(PCINT0/ADC0)PA0_37") (pintype "bidirectional"))
      (node (ref "R6") (pin "1") (pinfunction "1_1") (pintype "passive"))
    )
    (net (code "52") (name "PA0_") (class "Default")
      (node (ref "IC4") (pin "13") (pinfunction "(PCINT0/AREF/ADC0)PA0_13") (pintype "bidirectional"))
      (node (ref "PORT_A1") (pin "2") (pinfunction "2_2") (pintype "passive"))
    )
    (net (code "53") (name "PA1") (class "Default")
      (node (ref "IC1") (pin "36") (pinfunction "(PCINT1/ADC1)PA1_36") (pintype "bidirectional"))
      (node (ref "R7") (pin "1") (pinfunction "1_1") (pintype "passive"))
    )
    (net (code "54") (name "PA1_") (class "Default")
      (node (ref "IC4") (pin "12") (pinfunction "(PCINT1/AIN0/ADC1)PA1_12") (pintype "bidirectional"))
      (node (ref "PORT_A1") (pin "1") (pinfunction "1_1") (pintype "passive"))
    )
    (net (code "55") (name "PA2") (class "Default")
      (node (ref "IC1") (pin "35") (pinfunction "(PCINT2/ADC2)PA2_35") (pintype "bidirectional"))
      (node (ref "R9") (pin "1") (pinfunction "1_1") (pintype "passive"))
    )
    (net (code "56") (name "PA2_") (class "Default")
      (node (ref "IC4") (pin "11") (pinfunction "(PCINT2/AIN1/ADC2)PA2_11") (pintype "bidirectional"))
      (node (ref "PORT_A1") (pin "4") (pinfunction "4_4") (pintype "passive"))
    )
    (net (code "57") (name "PA3") (class "Default")
      (node (ref "IC1") (pin "34") (pinfunction "(PCINT3/ADC3)PA3_34") (pintype "bidirectional"))
      (node (ref "R10") (pin "1") (pinfunction "1_1") (pintype "passive"))
    )
    (net (code "58") (name "PA3_") (class "Default")
      (node (ref "IC4") (pin "10") (pinfunction "(PCINT3/T0/ADC3)PA3_10") (pintype "bidirectional"))
      (node (ref "PORT_A1") (pin "3") (pinfunction "3_3") (pintype "passive"))
    )
    (net (code "59") (name "PA4_") (class "Default")
      (node (ref "IC4") (pin "9") (pinfunction "(PCINT4/T1/SCL/USCK/ADC4)PA4_9") (pintype "bidirectional"))
      (node (ref "JP2") (pin "4") (pinfunction "4_4") (pintype "passive"))
      (node (ref "PORT_A1") (pin "6") (pinfunction "6_6") (pintype "passive"))
    )
    (net (code "60") (name "PA5") (class "Default")
      (node (ref "IC1") (pin "32") (pinfunction "(PCINT5/ADC5)PA5_32") (pintype "bidirectional"))
      (node (ref "R20") (pin "1") (pinfunction "1_1") (pintype "passive"))
    )
    (net (code "61") (name "PA5_") (class "Default")
      (node (ref "IC4") (pin "8") (pinfunction "(PCINT5/OC1B/MISO/DO/ADC5)PA5_8") (pintype "bidirectional"))
      (node (ref "JP2") (pin "6") (pinfunction "6_6") (pintype "passive"))
      (node (ref "PORT_A1") (pin "5") (pinfunction "5_5") (pintype "passive"))
    )
    (net (code "62") (name "PA6") (class "Default")
      (node (ref "IC1") (pin "31") (pinfunction "(PCINT6/ADC6)PA6_31") (pintype "bidirectional"))
      (node (ref "R19") (pin "1") (pinfunction "1_1") (pintype "passive"))
    )
    (net (code "63") (name "PA6_") (class "Default")
      (node (ref "IC4") (pin "7") (pinfunction "(PCINT6/OC1A/SDA/MOSI/ADC6)PA6_7") (pintype "bidirectional"))
      (node (ref "JP2") (pin "3") (pinfunction "3_3") (pintype "passive"))
      (node (ref "PORT_A1") (pin "8") (pinfunction "8_8") (pintype "passive"))
    )
    (net (code "64") (name "PA7") (class "Default")
      (node (ref "IC1") (pin "30") (pinfunction "(PCINT7/ADC7)PA7_30") (pintype "bidirectional"))
      (node (ref "R16") (pin "1") (pinfunction "1_1") (pintype "passive"))
    )
    (net (code "65") (name "PA7_") (class "Default")
      (node (ref "IC4") (pin "6") (pinfunction "(PCINT7/ICP/OC0B/ADC7)PA7_6") (pintype "bidirectional"))
      (node (ref "PORT_A1") (pin "7") (pinfunction "7_7") (pintype "passive"))
    )
    (net (code "66") (name "PB3_") (class "Default")
      (node (ref "IC4") (pin "4") (pinfunction "(PCINT11/RESET/DW)PB3_4") (pintype "bidirectional"))
      (node (ref "JP2") (pin "2") (pinfunction "2_2") (pintype "passive"))
      (node (ref "R10") (pin "2") (pinfunction "2_2") (pintype "passive"))
    )
    (net (code "67") (name "PB4") (class "Default")
      (node (ref "IC1") (pin "44") (pinfunction "(PCINT12/OC0B/~{SS})PB4_44") (pintype "bidirectional"))
      (node (ref "PIEZO-POWER9") (pin "1") (pinfunction "1_1") (pintype "passive"))
    )
    (net (code "68") (name "PB5") (class "Default")
      (node (ref "IC1") (pin "1") (pinfunction "(PCINT13/MOSI)PB5_1") (pintype "bidirectional"))
      (node (ref "PIEZO-POWER9") (pin "2") (pinfunction "2_2") (pintype "passive"))
    )
    (net (code "69") (name "PB6") (class "Default")
      (node (ref "IC1") (pin "2") (pinfunction "(PCINT14/MISO)PB6_2") (pintype "bidirectional"))
      (node (ref "PIEZO-POWER8") (pin "1") (pinfunction "1_1") (pintype "passive"))
    )
    (net (code "70") (name "PB7") (class "Default")
      (node (ref "IC1") (pin "3") (pinfunction "(PCINT15/SCK)PB7_3") (pintype "bidirectional"))
      (node (ref "PIEZO-POWER8") (pin "2") (pinfunction "2_2") (pintype "passive"))
    )
    (net (code "71") (name "PC0") (class "Default")
      (node (ref "IC1") (pin "19") (pinfunction "(PCINT16/SCL)PC0_19") (pintype "output"))
      (node (ref "R23") (pin "1") (pinfunction "1_1") (pintype "passive"))
    )
    (net (code "72") (name "PC1") (class "Default")
      (node (ref "IC1") (pin "20") (pinfunction "(PCINT17/SDA)PC1_20") (pintype "output"))
      (node (ref "R22") (pin "1") (pinfunction "1_1") (pintype "passive"))
    )
    (net (code "73") (name "PD0") (class "Default")
      (node (ref "IC1") (pin "9") (pinfunction "(PCINT24/RXD0)PD0_9") (pintype "bidirectional"))
      (node (ref "RN1") (pin "4") (pinfunction "TXD_4") (pintype "bidirectional"))
      (node (ref "V1") (pin "1") (pinfunction "G_1") (pintype "passive"))
    )
    (net (code "74") (name "PD1") (class "Default")
      (node (ref "IC1") (pin "10") (pinfunction "(PCINT25/TXD0)PD1_10") (pintype "bidirectional"))
      (node (ref "RN1") (pin "5") (pinfunction "RXD_5") (pintype "bidirectional"))
      (node (ref "V2") (pin "1") (pinfunction "G_1") (pintype "passive"))
    )
    (net (code "75") (name "PD2") (class "Default")
      (node (ref "IC1") (pin "11") (pinfunction "(PCINT26/INT0)PD2_11") (pintype "bidirectional"))
      (node (ref "JP1") (pin "1") (pinfunction "1_1") (pintype "passive"))
      (node (ref "V3") (pin "1") (pinfunction "G_1") (pintype "passive"))
    )
    (net (code "76") (name "PD3") (class "Default")
      (node (ref "IC1") (pin "12") (pinfunction "(PCINT27/INT1)PD3_12") (pintype "bidirectional"))
      (node (ref "JP1") (pin "4") (pinfunction "4_4") (pintype "passive"))
      (node (ref "PIEZO-POWER1") (pin "1") (pinfunction "1_1") (pintype "passive"))
      (node (ref "V4") (pin "1") (pinfunction "G_1") (pintype "passive"))
    )
    (net (code "77") (name "PD4") (class "Default")
      (node (ref "IC1") (pin "13") (pinfunction "(PCINT28/OC1B)PD4_13") (pintype "bidirectional"))
      (node (ref "PIEZO-POWER3") (pin "1") (pinfunction "1_1") (pintype "passive"))
    )
    (net (code "78") (name "PD5") (class "Default")
      (node (ref "IC1") (pin "14") (pinfunction "(PCINT29/OC1A)PD5_14") (pintype "bidirectional"))
      (node (ref "PIEZO-POWER5") (pin "2") (pinfunction "2_2") (pintype "passive"))
    )
    (net (code "79") (name "PD6") (class "Default")
      (node (ref "IC1") (pin "15") (pinfunction "(PCINT30/OC2B/ICP)PD6_15") (pintype "bidirectional"))
      (node (ref "PIEZO-POWER3") (pin "2") (pinfunction "2_2") (pintype "passive"))
    )
    (net (code "80") (name "PD7") (class "Default")
      (node (ref "IC1") (pin "16") (pinfunction "(PCINT31/OC2A)PD7_16") (pintype "bidirectional"))
      (node (ref "PIEZO-POWER5") (pin "1") (pinfunction "1_1") (pintype "passive"))
    )
    (net (code "81") (name "RX") (class "Default")
      (node (ref "JP1") (pin "3") (pinfunction "3_3") (pintype "passive"))
      (node (ref "JTAG") (pin "6") (pinfunction "6_6") (pintype "passive"))
      (node (ref "U$4") (pin "18") (pinfunction "18_18") (pintype "passive"))
    )
    (net (code "82") (name "TX") (class "Default")
      (node (ref "JP1") (pin "2") (pinfunction "2_2") (pintype "passive"))
      (node (ref "JTAG") (pin "8") (pinfunction "8_8") (pintype "passive"))
      (node (ref "U$4") (pin "15") (pinfunction "15_15") (pintype "passive"))
    )
    (net (code "83") (name "VCC") (class "Default")
      (node (ref "0_OHM_A") (pin "1") (pinfunction "1_1") (pintype "passive"))
      (node (ref "5V_DC") (pin "OUT") (pinfunction "OUT_OUT") (pintype "passive"))
      (node (ref "C10") (pin "1") (pinfunction "1_1") (pintype "passive"))
      (node (ref "C13") (pin "+") (pinfunction "+_+") (pintype "passive"))
      (node (ref "C2") (pin "1") (pinfunction "1_1") (pintype "passive"))
      (node (ref "C3") (pin "1") (pinfunction "1_1") (pintype "passive"))
      (node (ref "C4") (pin "1") (pinfunction "1_1") (pintype "passive"))
      (node (ref "C7") (pin "1") (pinfunction "1_1") (pintype "passive"))
      (node (ref "D2") (pin "A") (pinfunction "A_A") (pintype "passive"))
      (node (ref "IC1") (pin "17") (pinfunction "VCC_17") (pintype "power_in"))
      (node (ref "IC1") (pin "38") (pinfunction "VCC_38") (pintype "power_in"))
      (node (ref "IC1") (pin "5") (pinfunction "VCC_5") (pintype "power_in"))
      (node (ref "IC2") (pin "1") (pinfunction "IN_1") (pintype "input"))
      (node (ref "IC2") (pin "3") (pinfunction "ON/~{OFF}_3") (pintype "input"))
      (node (ref "IC4") (pin "1") (pinfunction "VCC_1") (pintype "power_in"))
      (node (ref "JP2") (pin "5") (pinfunction "5_5") (pintype "passive"))
      (node (ref "JTAG") (pin "4") (pinfunction "4_4") (pintype "passive"))
      (node (ref "L1") (pin "1") (pinfunction "1_1") (pintype "passive"))
      (node (ref "PIEZO-POWER2") (pin "1") (pinfunction "1_1") (pintype "passive"))
      (node (ref "PIEZO-POWER4") (pin "1") (pinfunction "1_1") (pintype "passive"))
      (node (ref "R12") (pin "2") (pinfunction "2_2") (pintype "passive"))
      (node (ref "R13") (pin "2") (pinfunction "2_2") (pintype "passive"))
      (node (ref "R14") (pin "2") (pinfunction "2_2") (pintype "passive"))
      (node (ref "R15") (pin "2") (pinfunction "2_2") (pintype "passive"))
      (node (ref "R21") (pin "1") (pinfunction "1_1") (pintype "passive"))
      (node (ref "R24") (pin "2") (pinfunction "2_2") (pintype "passive"))
      (node (ref "R5") (pin "2") (pinfunction "2_2") (pintype "passive"))
      (node (ref "R8") (pin "2") (pinfunction "2_2") (pintype "passive"))
      (node (ref "RN1") (pin "3") (pinfunction "VCC_3") (pintype "bidirectional"))
      (node (ref "S1") (pin "3") (pinfunction "3_3") (pintype "passive"))
      (node (ref "S1") (pin "4") (pinfunction "4_4") (pintype "passive"))
      (node (ref "S2") (pin "3") (pinfunction "3_3") (pintype "passive"))
      (node (ref "S2") (pin "4") (pinfunction "4_4") (pintype "passive"))
    )
    (net (code "84") (name "unconnected-(JTAG-Pad7)") (class "Default")
      (node (ref "JTAG") (pin "7") (pinfunction "7_7") (pintype "passive"))
    )
    (net (code "85") (name "unconnected-(PORT_A1-Pad9)") (class "Default")
      (node (ref "PORT_A1") (pin "9") (pinfunction "9_9") (pintype "passive"))
    )
    (net (code "86") (name "unconnected-(PORT_A1-Pad10)") (class "Default")
      (node (ref "PORT_A1") (pin "10") (pinfunction "10_10") (pintype "passive"))
    )
    (net (code "87") (name "unconnected-(RN1-CTS_I-Pad2)") (class "Default")
      (node (ref "RN1") (pin "2") (pinfunction "CTS_I_2") (pintype "bidirectional"))
    )
    (net (code "88") (name "unconnected-(RN1-RTS_O-Pad6)") (class "Default")
      (node (ref "RN1") (pin "6") (pinfunction "RTS_O_6") (pintype "bidirectional"))
    )
    (net (code "89") (name "unconnected-(U$2-PadREMOTE)") (class "Default")
      (node (ref "U$2") (pin "REMOTE") (pinfunction "REMOTE_REMOTE") (pintype "bidirectional"))
    )
    (net (code "90") (name "unconnected-(U$3-PadREMOTE)") (class "Default")
      (node (ref "U$3") (pin "REMOTE") (pinfunction "REMOTE_REMOTE") (pintype "bidirectional"))
    )
    (net (code "91") (name "unconnected-(U$4-Pad1)") (class "Default")
      (node (ref "U$4") (pin "1") (pinfunction "1_1") (pintype "passive"))
    )
    (net (code "92") (name "unconnected-(U$4-Pad2)") (class "Default")
      (node (ref "U$4") (pin "2") (pinfunction "2_2") (pintype "passive"))
    )
    (net (code "93") (name "unconnected-(U$4-Pad3)") (class "Default")
      (node (ref "U$4") (pin "3") (pinfunction "3_3") (pintype "passive"))
    )
    (net (code "94") (name "unconnected-(U$4-Pad4)") (class "Default")
      (node (ref "U$4") (pin "4") (pinfunction "4_4") (pintype "passive"))
    )
    (net (code "95") (name "unconnected-(U$4-Pad5)") (class "Default")
      (node (ref "U$4") (pin "5") (pinfunction "5_5") (pintype "passive"))
    )
    (net (code "96") (name "unconnected-(U$4-Pad6)") (class "Default")
      (node (ref "U$4") (pin "6") (pinfunction "6_6") (pintype "passive"))
    )
    (net (code "97") (name "unconnected-(U$4-Pad7)") (class "Default")
      (node (ref "U$4") (pin "7") (pinfunction "7_7") (pintype "passive"))
    )
    (net (code "98") (name "unconnected-(U$4-Pad8)") (class "Default")
      (node (ref "U$4") (pin "8") (pinfunction "8_8") (pintype "passive"))
    )
    (net (code "99") (name "unconnected-(U$4-Pad9)") (class "Default")
      (node (ref "U$4") (pin "9") (pinfunction "9_9") (pintype "passive"))
    )
    (net (code "100") (name "unconnected-(U$4-Pad10)") (class "Default")
      (node (ref "U$4") (pin "10") (pinfunction "10_10") (pintype "passive"))
    )
    (net (code "101") (name "unconnected-(U$4-Pad11)") (class "Default")
      (node (ref "U$4") (pin "11") (pinfunction "11_11") (pintype "passive"))
    )
    (net (code "102") (name "unconnected-(U$4-Pad12)") (class "Default")
      (node (ref "U$4") (pin "12") (pinfunction "12_12") (pintype "passive"))
    )
    (net (code "103") (name "unconnected-(U$4-Pad13)") (class "Default")
      (node (ref "U$4") (pin "13") (pinfunction "13_13") (pintype "passive"))
    )
    (net (code "104") (name "unconnected-(U$4-Pad14)") (class "Default")
      (node (ref "U$4") (pin "14") (pinfunction "14_14") (pintype "passive"))
    )
    (net (code "105") (name "unconnected-(U$4-Pad16)") (class "Default")
      (node (ref "U$4") (pin "16") (pinfunction "16_16") (pintype "passive"))
    )
    (net (code "106") (name "unconnected-(U$4-Pad17)") (class "Default")
      (node (ref "U$4") (pin "17") (pinfunction "17_17") (pintype "passive"))
    )
    (net (code "107") (name "unconnected-(U$4-Pad19)") (class "Default")
      (node (ref "U$4") (pin "19") (pinfunction "19_19") (pintype "passive"))
    )
    (net (code "108") (name "unconnected-(U$4-Pad20)") (class "Default")
      (node (ref "U$4") (pin "20") (pinfunction "20_20") (pintype "passive"))
    )
    (net (code "109") (name "unconnected-(U$4-Pad21)") (class "Default")
      (node (ref "U$4") (pin "21") (pinfunction "21_21") (pintype "passive"))
    )
    (net (code "110") (name "unconnected-(U$4-Pad22)") (class "Default")
      (node (ref "U$4") (pin "22") (pinfunction "22_22") (pintype "passive"))
    )
    (net (code "111") (name "unconnected-(U$4-Pad23)") (class "Default")
      (node (ref "U$4") (pin "23") (pinfunction "23_23") (pintype "passive"))
    )
    (net (code "112") (name "unconnected-(U$4-Pad24)") (class "Default")
      (node (ref "U$4") (pin "24") (pinfunction "24_24") (pintype "passive"))
    )
    (net (code "113") (name "unconnected-(U$4-Pad25)") (class "Default")
      (node (ref "U$4") (pin "25") (pinfunction "25_25") (pintype "passive"))
    )
    (net (code "114") (name "unconnected-(U$4-Pad26)") (class "Default")
      (node (ref "U$4") (pin "26") (pinfunction "26_26") (pintype "passive"))
    )
    (net (code "115") (name "unconnected-(U$4-Pad27)") (class "Default")
      (node (ref "U$4") (pin "27") (pinfunction "27_27") (pintype "passive"))
    )
    (net (code "116") (name "unconnected-(U$4-Pad28)") (class "Default")
      (node (ref "U$4") (pin "28") (pinfunction "28_28") (pintype "passive"))
    )
    (net (code "117") (name "unconnected-(U$4-Pad29)") (class "Default")
      (node (ref "U$4") (pin "29") (pinfunction "29_29") (pintype "passive"))
    )
    (net (code "118") (name "unconnected-(U$4-Pad30)") (class "Default")
      (node (ref "U$4") (pin "30") (pinfunction "30_30") (pintype "passive"))
    )
    (net (code "119") (name "unconnected-(U$4-Pad33)") (class "Default")
      (node (ref "U$4") (pin "33") (pinfunction "33_33") (pintype "passive"))
    )
    (net (code "120") (name "unconnected-(U$4-Pad34)") (class "Default")
      (node (ref "U$4") (pin "34") (pinfunction "34_34") (pintype "passive"))
    )
    (net (code "121") (name "unconnected-(X1-Pad2)") (class "Default")
      (node (ref "X1") (pin "2") (pinfunction "2_2") (pintype "passive"))
    )
    (net (code "122") (name "unconnected-(X1-Pad3)") (class "Default")
      (node (ref "X1") (pin "3") (pinfunction "3_3") (pintype "passive"))
    )
  )
)
